# STM32F108VBT6.net
KiCad netlist of a schematic drawn in Altium Designer
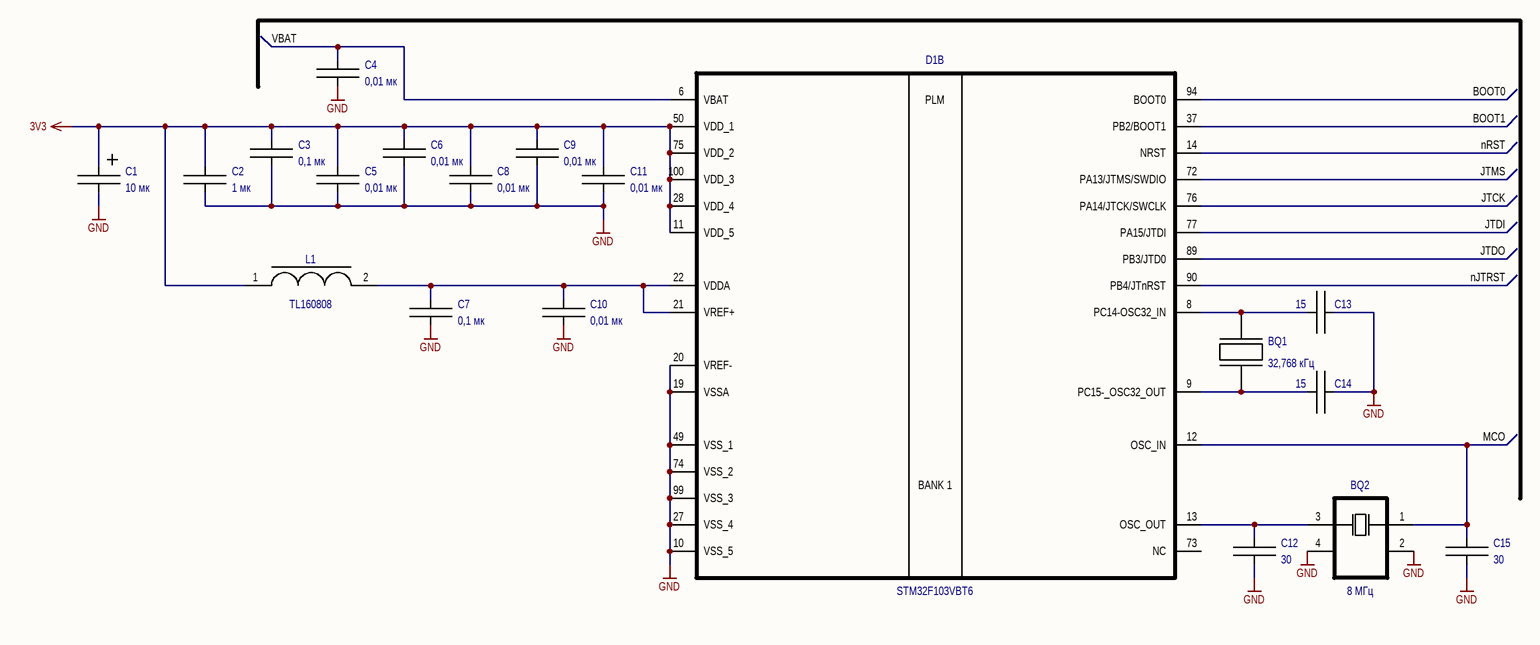
[diagram p0: Модуль STM32F108VBT6.SchDoc]

(export (version "E")
  (design (tool "Eeschema 10.0.6"))
  (components
    (comp (ref "BQ1")
      (value "32,768 кГц")
      (footprint "SMD3215_2P32768KHZ125PF10PPM")
      (fields (field (name "PARTNUMBER") "32,768 кГц 3215 SMD") (field (name "Comment") "3215"))
      (libsource (lib "Lisaveta") (part "кварцевый резонатор"))
    )
    (comp (ref "BQ2")
      (value "8 МГц")
      (footprint "SMD3225_4P20MHZ20PF10PPM")
      (fields (field (name "PARTNUMBER") "MQ-12.000-18") (field (name "Comment") "кварцевый резонатор_1"))
      (libsource (lib "Lisaveta_SCH") (part "кварцевый резонатор_1"))
    )
    (comp (ref "C1")
      (value "10 мк")
      (footprint "K53-68_3216(A)")
      (fields (field (name "Comment") "A-case"))
      (libsource (lib "Lisaveta_SCH") (part "C+"))
    )
    (comp (ref "C2")
      (value "1 мк")
      (footprint "K10-69B_2.0_1.25(0805)")
      (fields (field (name "Comment") "0805"))
      (libsource (lib "Lisaveta") (part "C"))
    )
    (comp (ref "C3")
      (value "0,1 мк")
      (footprint "K10-79_1.6_0.8(0603)")
      (fields (field (name "Comment") "0603"))
      (libsource (lib "Lisaveta") (part "C"))
    )
    (comp (ref "C4")
      (value "0,01 мк")
      (footprint "K10-79_1.6_0.8(0603)")
      (fields (field (name "Comment") "0603"))
      (libsource (lib "Lisaveta") (part "C"))
    )
    (comp (ref "C5")
      (value "0,01 мк")
      (footprint "K10-79_1.6_0.8(0603)")
      (fields (field (name "Comment") "0603"))
      (libsource (lib "Lisaveta") (part "C"))
    )
    (comp (ref "C6")
      (value "0,01 мк")
      (footprint "K10-79_1.6_0.8(0603)")
      (fields (field (name "Comment") "0603"))
      (libsource (lib "Lisaveta") (part "C"))
    )
    (comp (ref "C7")
      (value "0,1 мк")
      (footprint "K10-79_1.6_0.8(0603)")
      (fields (field (name "Comment") "0603"))
      (libsource (lib "Lisaveta") (part "C"))
    )
    (comp (ref "C8")
      (value "0,01 мк")
      (footprint "K10-79_1.6_0.8(0603)")
      (fields (field (name "Comment") "0603"))
      (libsource (lib "Lisaveta") (part "C"))
    )
    (comp (ref "C9")
      (value "0,01 мк")
      (footprint "K10-79_1.6_0.8(0603)")
      (fields (field (name "Comment") "0603"))
      (libsource (lib "Lisaveta") (part "C"))
    )
    (comp (ref "C10")
      (value "0,01 мк")
      (footprint "K10-79_1.6_0.8(0603)")
      (fields (field (name "Comment") "0603"))
      (libsource (lib "Lisaveta") (part "C"))
    )
    (comp (ref "C11")
      (value "0,01 мк")
      (footprint "K10-79_1.6_0.8(0603)")
      (fields (field (name "Comment") "0603"))
      (libsource (lib "Lisaveta") (part "C"))
    )
    (comp (ref "C12")
      (value "30")
      (footprint "K10-79_1.6_0.8(0603)")
      (fields (field (name "Comment") "0603"))
      (libsource (lib "Lisaveta") (part "C"))
    )
    (comp (ref "C13")
      (value "15")
      (footprint "K10-79_1.6_0.8(0603)")
      (fields (field (name "Comment") "0603"))
      (libsource (lib "Lisaveta") (part "C"))
    )
    (comp (ref "C14")
      (value "15")
      (footprint "K10-79_1.6_0.8(0603)")
      (fields (field (name "Comment") "0603"))
      (libsource (lib "Lisaveta") (part "C"))
    )
    (comp (ref "C15")
      (value "30")
      (footprint "K10-79_1.6_0.8(0603)")
      (fields (field (name "Comment") "0603"))
      (libsource (lib "Lisaveta") (part "C"))
    )
    (comp (ref "D1")
      (value "STM32F103VBT6")
      (footprint "QFP50P1600X1600X160-100N")
      (fields (field (name "Comment") " (LQFP-48) Xilinx"))
      (libsource (lib "Lisaveta_SCH") (part "STM32F103VBT6"))
    )
    (comp (ref "L1")
      (value "TL160808")
      (footprint "742792651")
      (fields (field (name "Comment") "0603"))
      (libsource (lib "Lisaveta") (part "SH6028-5R0YLB"))
    )
  )
  (nets
    (net (code "1") (name "/BOOT0") (class "Default")
      (node (ref "D1") (pin "94") (pinfunction "BOOT0_94") (pintype "passive"))
    )
    (net (code "2") (name "/BOOT1") (class "Default")
      (node (ref "D1") (pin "37") (pinfunction "PB2/BOOT1_37") (pintype "passive"))
    )
    (net (code "3") (name "/JTCK") (class "Default")
      (node (ref "D1") (pin "76") (pinfunction "PA14/JTCK/SWCLK_76") (pintype "passive"))
    )
    (net (code "4") (name "/JTDI") (class "Default")
      (node (ref "D1") (pin "77") (pinfunction "PA15/JTDI_77") (pintype "passive"))
    )
    (net (code "5") (name "/JTDO") (class "Default")
      (node (ref "D1") (pin "89") (pinfunction "PB3/JTD0_89") (pintype "passive"))
    )
    (net (code "6") (name "/JTMS") (class "Default")
      (node (ref "D1") (pin "72") (pinfunction "PA13/JTMS/SWDIO_72") (pintype "passive"))
    )
    (net (code "7") (name "/MCO") (class "Default")
      (node (ref "BQ2") (pin "1") (pinfunction "1_1") (pintype "passive"))
      (node (ref "C15") (pin "2") (pinfunction "2_2") (pintype "passive"))
      (node (ref "D1") (pin "12") (pinfunction "OSC_IN_12") (pintype "passive"))
    )
    (net (code "8") (name "/VBAT") (class "Default")
      (node (ref "C4") (pin "2") (pinfunction "2_2") (pintype "passive"))
      (node (ref "D1") (pin "6") (pinfunction "VBAT_6") (pintype "passive"))
    )
    (net (code "9") (name "/nJTRST") (class "Default")
      (node (ref "D1") (pin "90") (pinfunction "PB4/JTnRST_90") (pintype "passive"))
    )
    (net (code "10") (name "/nRST") (class "Default")
      (node (ref "D1") (pin "14") (pinfunction "NRST_14") (pintype "passive"))
    )
    (net (code "11") (name "3V3") (class "Default")
      (node (ref "C1") (pin "1") (pinfunction "1_1") (pintype "passive"))
      (node (ref "C11") (pin "2") (pinfunction "2_2") (pintype "passive"))
      (node (ref "C2") (pin "2") (pinfunction "2_2") (pintype "passive"))
      (node (ref "C3") (pin "2") (pinfunction "2_2") (pintype "passive"))
      (node (ref "C5") (pin "2") (pinfunction "2_2") (pintype "passive"))
      (node (ref "C6") (pin "2") (pinfunction "2_2") (pintype "passive"))
      (node (ref "C8") (pin "2") (pinfunction "2_2") (pintype "passive"))
      (node (ref "C9") (pin "2") (pinfunction "2_2") (pintype "passive"))
      (node (ref "D1") (pin "100") (pinfunction "VDD_3_100") (pintype "passive"))
      (node (ref "D1") (pin "11") (pinfunction "VDD_5_11") (pintype "passive"))
      (node (ref "D1") (pin "28") (pinfunction "VDD_4_28") (pintype "passive"))
      (node (ref "D1") (pin "50") (pinfunction "VDD_1_50") (pintype "passive"))
      (node (ref "D1") (pin "75") (pinfunction "VDD_2_75") (pintype "passive"))
      (node (ref "L1") (pin "1") (pinfunction "1_1") (pintype "passive"))
    )
    (net (code "12") (name "GND") (class "Default")
      (node (ref "BQ2") (pin "2") (pinfunction "GND_2") (pintype "passive"))
      (node (ref "BQ2") (pin "4") (pinfunction "GND_4") (pintype "passive"))
      (node (ref "C1") (pin "2") (pinfunction "2_2") (pintype "passive"))
      (node (ref "C10") (pin "1") (pinfunction "1_1") (pintype "passive"))
      (node (ref "C11") (pin "1") (pinfunction "1_1") (pintype "passive"))
      (node (ref "C12") (pin "1") (pinfunction "1_1") (pintype "passive"))
      (node (ref "C13") (pin "1") (pinfunction "1_1") (pintype "passive"))
      (node (ref "C14") (pin "1") (pinfunction "1_1") (pintype "passive"))
      (node (ref "C15") (pin "1") (pinfunction "1_1") (pintype "passive"))
      (node (ref "C2") (pin "1") (pinfunction "1_1") (pintype "passive"))
      (node (ref "C3") (pin "1") (pinfunction "1_1") (pintype "passive"))
      (node (ref "C4") (pin "1") (pinfunction "1_1") (pintype "passive"))
      (node (ref "C5") (pin "1") (pinfunction "1_1") (pintype "passive"))
      (node (ref "C6") (pin "1") (pinfunction "1_1") (pintype "passive"))
      (node (ref "C7") (pin "1") (pinfunction "1_1") (pintype "passive"))
      (node (ref "C8") (pin "1") (pinfunction "1_1") (pintype "passive"))
      (node (ref "C9") (pin "1") (pinfunction "1_1") (pintype "passive"))
      (node (ref "D1") (pin "10") (pinfunction "VSS_5_10") (pintype "passive"))
      (node (ref "D1") (pin "19") (pinfunction "VSSA_19") (pintype "passive"))
      (node (ref "D1") (pin "20") (pinfunction "VREF-_20") (pintype "passive"))
      (node (ref "D1") (pin "27") (pinfunction "VSS_4_27") (pintype "passive"))
      (node (ref "D1") (pin "49") (pinfunction "VSS_1_49") (pintype "passive"))
      (node (ref "D1") (pin "74") (pinfunction "VSS_2_74") (pintype "passive"))
      (node (ref "D1") (pin "99") (pinfunction "VSS_3_99") (pintype "passive"))
    )
    (net (code "13") (name "Net-(BQ1-GND)") (class "Default")
      (node (ref "BQ1") (pin "2") (pinfunction "GND_2") (pintype "passive"))
      (node (ref "C14") (pin "2") (pinfunction "2_2") (pintype "passive"))
      (node (ref "D1") (pin "9") (pinfunction "PC15-_OSC32_OUT_9") (pintype "passive"))
    )
    (net (code "14") (name "Net-(BQ1-IN)") (class "Default")
      (node (ref "BQ1") (pin "1") (pinfunction "IN_1") (pintype "passive"))
      (node (ref "C13") (pin "2") (pinfunction "2_2") (pintype "passive"))
      (node (ref "D1") (pin "8") (pinfunction "PC14-OSC32_IN_8") (pintype "passive"))
    )
    (net (code "15") (name "Net-(D1B-OSC_OUT)") (class "Default")
      (node (ref "BQ2") (pin "3") (pinfunction "3_3") (pintype "passive"))
      (node (ref "C12") (pin "2") (pinfunction "2_2") (pintype "passive"))
      (node (ref "D1") (pin "13") (pinfunction "OSC_OUT_13") (pintype "passive"))
    )
    (net (code "16") (name "Net-(D1B-VDDA)") (class "Default")
      (node (ref "C10") (pin "2") (pinfunction "2_2") (pintype "passive"))
      (node (ref "C7") (pin "2") (pinfunction "2_2") (pintype "passive"))
      (node (ref "D1") (pin "21") (pinfunction "VREF+_21") (pintype "passive"))
      (node (ref "D1") (pin "22") (pinfunction "VDDA_22") (pintype "passive"))
      (node (ref "L1") (pin "2") (pinfunction "2_2") (pintype "passive"))
    )
    (net (code "17") (name "unconnected-(D1B-NC-Pad73)") (class "Default")
      (node (ref "D1") (pin "73") (pinfunction "NC_73") (pintype "passive"))
    )
  )
)
